# TOUCH1.net
KiCad netlist of a schematic drawn in Altium Designer
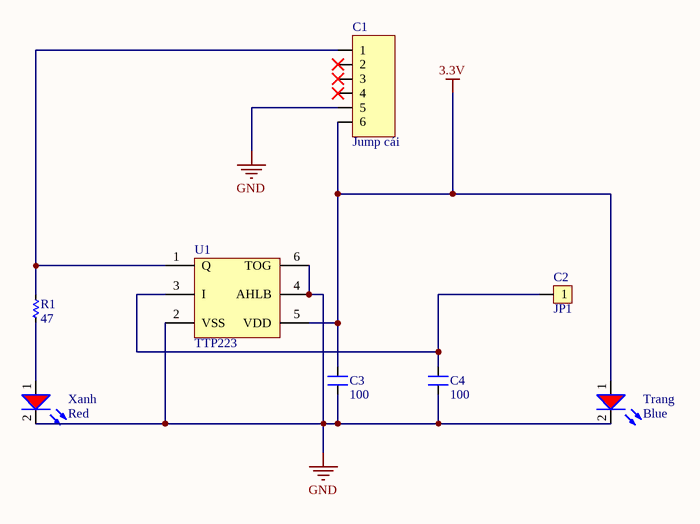
[diagram p0: TOUCH1.SchDoc]

(export (version "E")
  (design (tool "Eeschema 10.0.6"))
  (components
    (comp (ref "C1")
      (value "Jump cái")
      (footprint "JP6-C1T")
      (description "WR-PHD 2.54 mm Angled Socket Header")
      (fields
        (field (name "MANUFACTURER") "Würth Elektronik eiSos GmbH")
        (field (name "PARTNO") "613006143121")
        (field (name "CREATED BY") "Karrer Zheng")
      )
      (libsource (lib "TechMT.VN_Lib_Project v2") (part "JP6"))
    )
    (comp (ref "C2")
      (value "JP1")
      (footprint "JP1-D1T")
      (description "WR-PHD 2.54 mm Angled Socket Header")
      (fields
        (field (name "MANUFACTURER") "Würth Elektronik eiSos GmbH")
        (field (name "PARTNO") "613002143121")
        (field (name "CREATED BY") "Karrer Zheng")
      )
      (libsource (lib "TechMT.VN_Lib_Project v2") (part "JP1"))
    )
    (comp (ref "C3")
      (value "100")
      (footprint "SM-0805")
      (description "Cap SMD")
      (libsource (lib "syhaunguyen") (part "CM"))
    )
    (comp (ref "C4")
      (value "100")
      (footprint "SM-0805")
      (description "Cap SMD")
      (libsource (lib "syhaunguyen") (part "CM"))
    )
    (comp (ref "R1")
      (value "47")
      (footprint "RES-SMD-0805")
      (description "Resistor")
      (fields
        (field (name "MANUFACTURER") "Generic Components")
        (field (name "PUBLISHER") "Altium Hobart Technology Centre")
      )
      (libsource (lib "TechMT.VN_Lib_Project v2") (part "Res-SMD"))
    )
    (comp (ref "Trang")
      (value "Blue")
      (footprint "LED-RED-0805")
      (description "LED Red 2mA 1.8V 0805")
      (fields (field (name "Comment") "LED-Red"))
      (libsource (lib "TechMT.VN_Lib_Project v2") (part "Led-Red"))
    )
    (comp (ref "U1")
      (value "TTP223")
      (footprint "SOT23-6")
      (description "Half-Bridge Driver")
      (libsource (lib "TechMT.VN_Lib_Project v2") (part "TTP223"))
    )
    (comp (ref "Xanh")
      (value "Red")
      (footprint "LED-RED-0805")
      (description "LED Red 2mA 1.8V 0805")
      (fields (field (name "Comment") "LED-Red"))
      (libsource (lib "TechMT.VN_Lib_Project v2") (part "Led-Red"))
    )
  )
  (nets
    (net (code "1") (name "3.3V") (class "Default")
      (node (ref "C1") (pin "6") (pinfunction "6_6") (pintype "passive"))
      (node (ref "C3") (pin "1") (pinfunction "1_1") (pintype "passive"))
      (node (ref "Trang") (pin "1") (pinfunction "A_1") (pintype "passive"))
      (node (ref "U1") (pin "5") (pinfunction "VDD_5") (pintype "passive"))
    )
    (net (code "2") (name "GND") (class "Default")
      (node (ref "C1") (pin "5") (pinfunction "5_5") (pintype "passive"))
      (node (ref "C3") (pin "2") (pinfunction "2_2") (pintype "passive"))
      (node (ref "C4") (pin "2") (pinfunction "2_2") (pintype "passive"))
      (node (ref "Trang") (pin "2") (pinfunction "K_2") (pintype "passive"))
      (node (ref "U1") (pin "2") (pinfunction "VSS_2") (pintype "passive"))
      (node (ref "U1") (pin "4") (pinfunction "AHLB_4") (pintype "passive"))
      (node (ref "U1") (pin "6") (pinfunction "TOG_6") (pintype "passive"))
      (node (ref "Xanh") (pin "2") (pinfunction "K_2") (pintype "passive"))
    )
    (net (code "3") (name "Net-(U1-I)") (class "Default")
      (node (ref "C2") (pin "1") (pinfunction "1_1") (pintype "passive"))
      (node (ref "C4") (pin "1") (pinfunction "1_1") (pintype "passive"))
      (node (ref "U1") (pin "3") (pinfunction "I_3") (pintype "passive"))
    )
    (net (code "4") (name "Net-(U1-Q)") (class "Default")
      (node (ref "C1") (pin "1") (pinfunction "1_1") (pintype "passive"))
      (node (ref "R1") (pin "1") (pinfunction "1_1") (pintype "passive"))
      (node (ref "U1") (pin "1") (pinfunction "Q_1") (pintype "passive"))
    )
    (net (code "5") (name "Net-(Xanh-A)") (class "Default")
      (node (ref "R1") (pin "2") (pinfunction "2_2") (pintype "passive"))
      (node (ref "Xanh") (pin "1") (pinfunction "A_1") (pintype "passive"))
    )
    (net (code "6") (name "unconnected-(C1-Pad2)") (class "Default")
      (node (ref "C1") (pin "2") (pinfunction "2_2") (pintype "passive+no_connect"))
    )
    (net (code "7") (name "unconnected-(C1-Pad3)") (class "Default")
      (node (ref "C1") (pin "3") (pinfunction "3_3") (pintype "passive+no_connect"))
    )
    (net (code "8") (name "unconnected-(C1-Pad4)") (class "Default")
      (node (ref "C1") (pin "4") (pinfunction "4_4") (pintype "passive+no_connect"))
    )
  )
)
